# Taito_Arkanoid_paddle.net
KiCad netlist of a schematic drawn in EAGLE
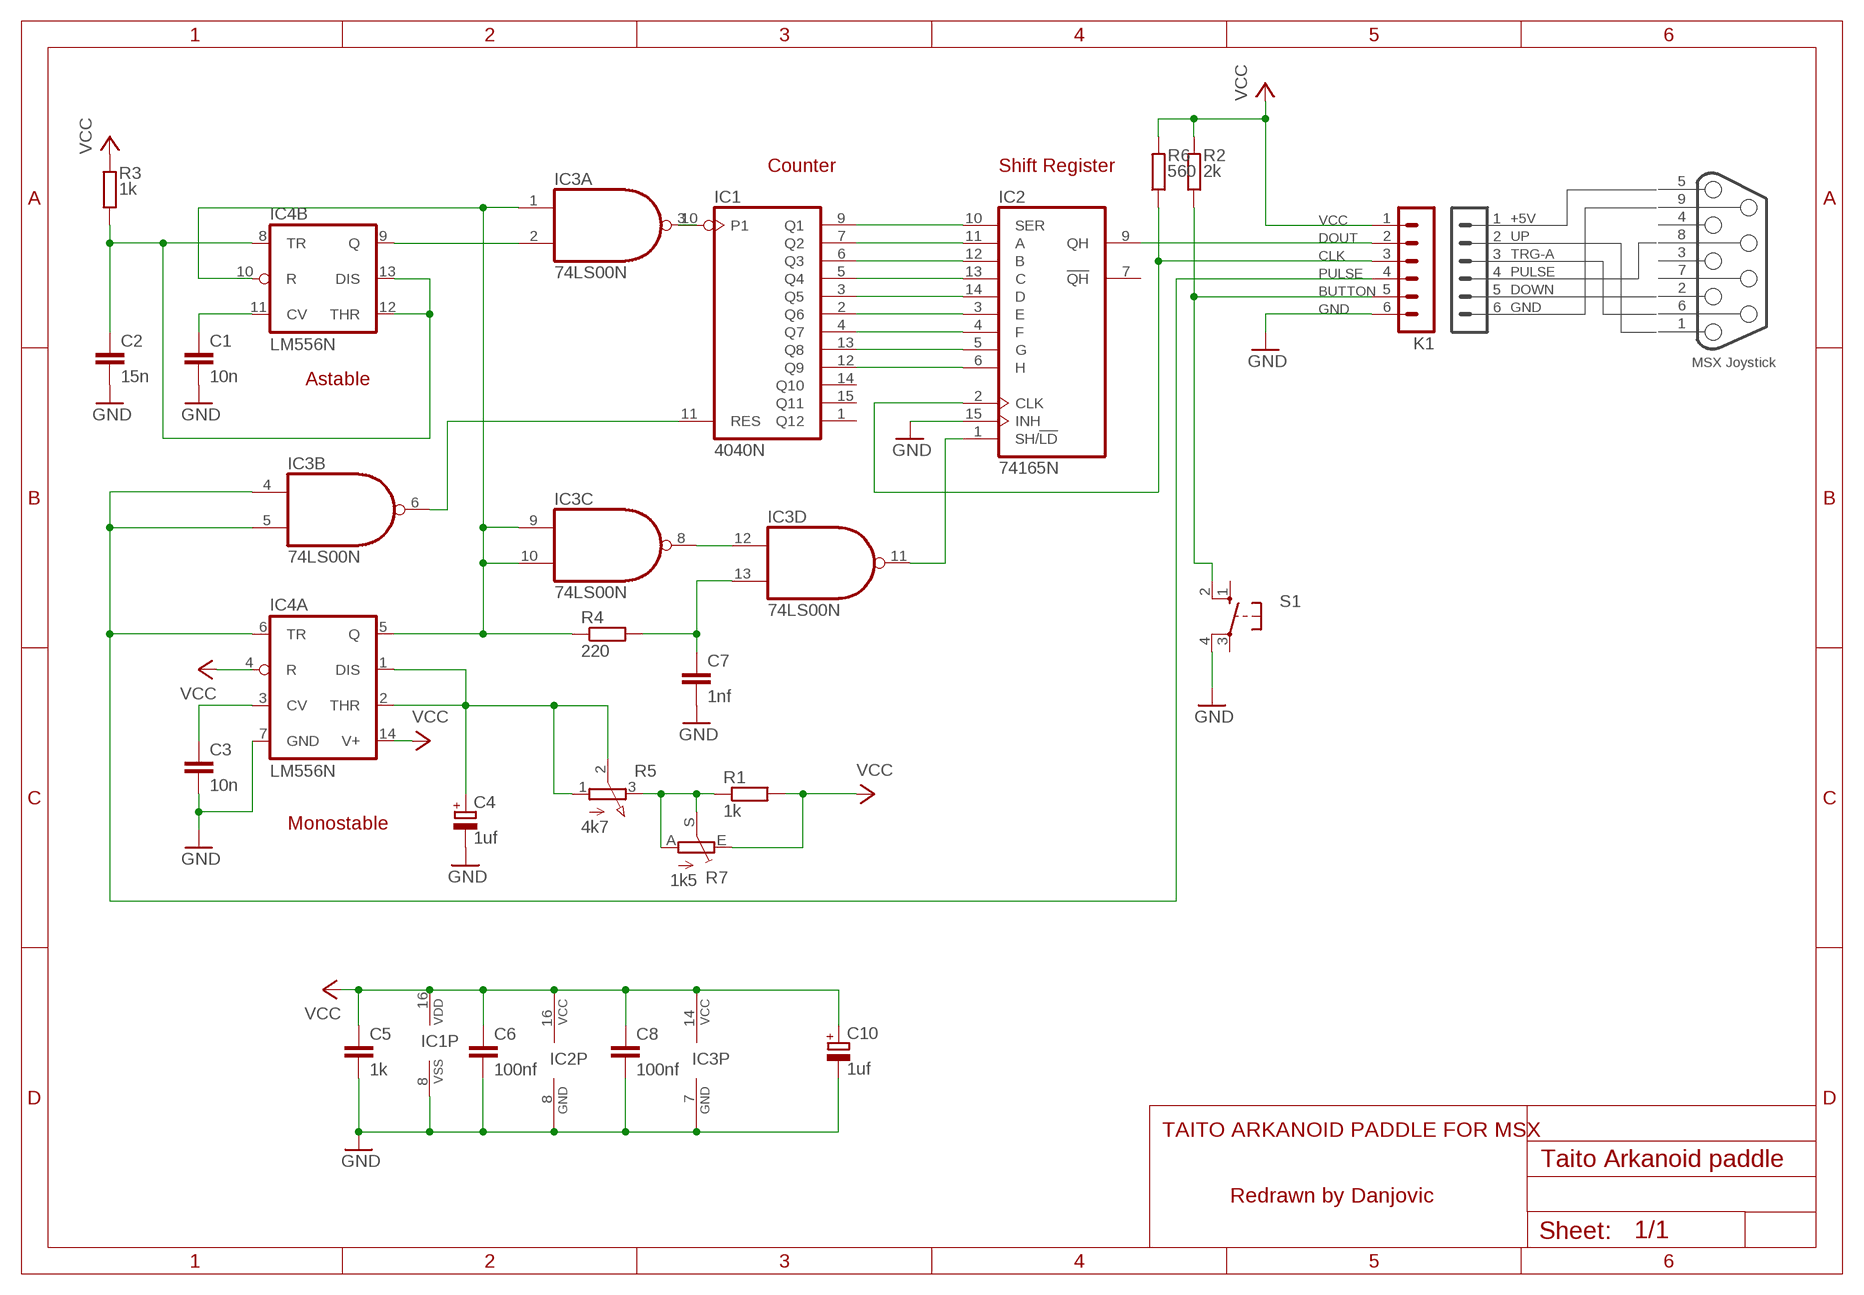
[diagram p0: schematic, sheet 1]

(export (version "E")
  (design (tool "Eeschema 10.0.6"))
  (components
    (comp (ref "C1")
      (value "10n")
      (footprint "eagle-import:C050-024X044")
      (libsource (lib "eagle-import") (part "C-EU050-024X044"))
    )
    (comp (ref "C2")
      (value "15n")
      (footprint "eagle-import:C050-024X044")
      (libsource (lib "eagle-import") (part "C-EU050-024X044"))
    )
    (comp (ref "C3")
      (value "10n")
      (footprint "eagle-import:C050-024X044")
      (libsource (lib "eagle-import") (part "C-EU050-024X044"))
    )
    (comp (ref "C4")
      (value "1uf")
      (footprint "eagle-import:E2-4")
      (libsource (lib "eagle-import") (part "CPOL-EUE2-4"))
    )
    (comp (ref "C5")
      (value "1k")
      (footprint "eagle-import:C050-024X044")
      (libsource (lib "eagle-import") (part "C-EU050-024X044"))
    )
    (comp (ref "C6")
      (value "100nf")
      (footprint "eagle-import:C050-024X044")
      (libsource (lib "eagle-import") (part "C-EU050-024X044"))
    )
    (comp (ref "C7")
      (value "1nf")
      (footprint "eagle-import:C050-024X044")
      (libsource (lib "eagle-import") (part "C-EU050-024X044"))
    )
    (comp (ref "C8")
      (value "100nf")
      (footprint "eagle-import:C050-024X044")
      (libsource (lib "eagle-import") (part "C-EU050-024X044"))
    )
    (comp (ref "C10")
      (value "1uf")
      (footprint "eagle-import:E2-4")
      (libsource (lib "eagle-import") (part "CPOL-EUE2-4"))
    )
    (comp (ref "IC1")
      (value "4040N")
      (footprint "eagle-import:DIL16")
      (libsource (lib "eagle-import") (part "4040N"))
    )
    (comp (ref "IC2")
      (value "74165N")
      (footprint "eagle-import:DIL16")
      (libsource (lib "eagle-import") (part "74165N"))
    )
    (comp (ref "IC3")
      (value "74LS00N")
      (footprint "eagle-import:DIL14")
      (libsource (lib "eagle-import") (part "7400NLS"))
    )
    (comp (ref "IC4")
      (value "LM556N")
      (footprint "eagle-import:DIL14")
      (libsource (lib "eagle-import") (part "556NLM"))
    )
    (comp (ref "K1")
      (value "MA06-1")
      (footprint "eagle-import:MA06-1")
      (libsource (lib "eagle-import") (part "MA06-1"))
    )
    (comp (ref "R1")
      (value "1k")
      (footprint "eagle-import:0207_7")
      (libsource (lib "eagle-import") (part "R-EU_0207/7"))
    )
    (comp (ref "R2")
      (value "2k")
      (footprint "eagle-import:0207_7")
      (libsource (lib "eagle-import") (part "R-EU_0207/7"))
    )
    (comp (ref "R3")
      (value "1k")
      (footprint "eagle-import:0207_7")
      (libsource (lib "eagle-import") (part "R-EU_0207/7"))
    )
    (comp (ref "R4")
      (value "220")
      (footprint "eagle-import:0207_7")
      (libsource (lib "eagle-import") (part "R-EU_0207/7"))
    )
    (comp (ref "R5")
      (value "4k7")
      (footprint "eagle-import:3RP_1610N_THRU")
      (libsource (lib "eagle-import") (part "3RP/1610NTHRU"))
    )
    (comp (ref "R6")
      (value "560")
      (footprint "eagle-import:0207_7")
      (libsource (lib "eagle-import") (part "R-EU_0207/7"))
    )
    (comp (ref "R7")
      (value "1k5")
      (footprint "eagle-import:CT6")
      (libsource (lib "eagle-import") (part "TRIM_EU-CT6"))
    )
    (comp (ref "S1")
      (value "40-XX")
      (footprint "eagle-import:B3F-40XX")
      (fields (field (name "MF") "OMRON COMPONENTS USA") (field (name "MPN") "B3F-4000"))
      (libsource (lib "eagle-import") (part "40-XX"))
    )
  )
  (nets
    (net (code "1") (name "/BUTTON") (class "Default")
      (node (ref "K1") (pin "5") (pinfunction "5_5") (pintype "passive"))
      (node (ref "R2") (pin "1") (pinfunction "1_1") (pintype "passive"))
      (node (ref "S1") (pin "2") (pinfunction "S1_2") (pintype "passive"))
    )
    (net (code "2") (name "/CLK") (class "Default")
      (node (ref "IC2") (pin "2") (pinfunction "CLK_2") (pintype "input"))
      (node (ref "K1") (pin "3") (pinfunction "3_3") (pintype "passive"))
      (node (ref "R6") (pin "1") (pinfunction "1_1") (pintype "passive"))
    )
    (net (code "3") (name "/DOUT") (class "Default")
      (node (ref "IC2") (pin "9") (pinfunction "QH_9") (pintype "output"))
      (node (ref "K1") (pin "2") (pinfunction "2_2") (pintype "passive"))
    )
    (net (code "4") (name "/PULSE") (class "Default")
      (node (ref "IC3") (pin "4") (pinfunction "I0_4") (pintype "input"))
      (node (ref "IC3") (pin "5") (pinfunction "I1_5") (pintype "input"))
      (node (ref "IC4") (pin "6") (pinfunction "TR_6") (pintype "input"))
      (node (ref "K1") (pin "4") (pinfunction "4_4") (pintype "passive"))
    )
    (net (code "5") (name "GND") (class "Default")
      (node (ref "C1") (pin "2") (pinfunction "2_2") (pintype "passive"))
      (node (ref "C10") (pin "-") (pinfunction "-_-") (pintype "passive"))
      (node (ref "C2") (pin "2") (pinfunction "2_2") (pintype "passive"))
      (node (ref "C3") (pin "2") (pinfunction "2_2") (pintype "passive"))
      (node (ref "C4") (pin "-") (pinfunction "-_-") (pintype "passive"))
      (node (ref "C5") (pin "2") (pinfunction "2_2") (pintype "passive"))
      (node (ref "C6") (pin "2") (pinfunction "2_2") (pintype "passive"))
      (node (ref "C7") (pin "2") (pinfunction "2_2") (pintype "passive"))
      (node (ref "C8") (pin "2") (pinfunction "2_2") (pintype "passive"))
      (node (ref "IC1") (pin "8") (pinfunction "VSS_8") (pintype "power_in"))
      (node (ref "IC2") (pin "15") (pinfunction "INH_15") (pintype "input"))
      (node (ref "IC2") (pin "8") (pinfunction "GND_8") (pintype "power_in"))
      (node (ref "IC3") (pin "7") (pinfunction "GND_7") (pintype "power_in"))
      (node (ref "IC4") (pin "7") (pinfunction "GND_7") (pintype "power_in"))
      (node (ref "K1") (pin "6") (pinfunction "6_6") (pintype "passive"))
      (node (ref "S1") (pin "4") (pinfunction "P1_4") (pintype "passive"))
    )
    (net (code "6") (name "Net-(IC1A-P1)") (class "Default")
      (node (ref "IC1") (pin "10") (pinfunction "P1_10") (pintype "input"))
      (node (ref "IC3") (pin "3") (pinfunction "O_3") (pintype "output"))
    )
    (net (code "7") (name "Net-(IC1A-Q1)") (class "Default")
      (node (ref "IC1") (pin "9") (pinfunction "Q1_9") (pintype "output"))
      (node (ref "IC2") (pin "10") (pinfunction "SER_10") (pintype "input"))
    )
    (net (code "8") (name "Net-(IC1A-Q2)") (class "Default")
      (node (ref "IC1") (pin "7") (pinfunction "Q2_7") (pintype "output"))
      (node (ref "IC2") (pin "11") (pinfunction "A_11") (pintype "input"))
    )
    (net (code "9") (name "Net-(IC1A-Q3)") (class "Default")
      (node (ref "IC1") (pin "6") (pinfunction "Q3_6") (pintype "output"))
      (node (ref "IC2") (pin "12") (pinfunction "B_12") (pintype "input"))
    )
    (net (code "10") (name "Net-(IC1A-Q4)") (class "Default")
      (node (ref "IC1") (pin "5") (pinfunction "Q4_5") (pintype "output"))
      (node (ref "IC2") (pin "13") (pinfunction "C_13") (pintype "input"))
    )
    (net (code "11") (name "Net-(IC1A-Q5)") (class "Default")
      (node (ref "IC1") (pin "3") (pinfunction "Q5_3") (pintype "output"))
      (node (ref "IC2") (pin "14") (pinfunction "D_14") (pintype "input"))
    )
    (net (code "12") (name "Net-(IC1A-Q6)") (class "Default")
      (node (ref "IC1") (pin "2") (pinfunction "Q6_2") (pintype "output"))
      (node (ref "IC2") (pin "3") (pinfunction "E_3") (pintype "input"))
    )
    (net (code "13") (name "Net-(IC1A-Q7)") (class "Default")
      (node (ref "IC1") (pin "4") (pinfunction "Q7_4") (pintype "output"))
      (node (ref "IC2") (pin "4") (pinfunction "F_4") (pintype "input"))
    )
    (net (code "14") (name "Net-(IC1A-Q8)") (class "Default")
      (node (ref "IC1") (pin "13") (pinfunction "Q8_13") (pintype "output"))
      (node (ref "IC2") (pin "5") (pinfunction "G_5") (pintype "input"))
    )
    (net (code "15") (name "Net-(IC1A-Q9)") (class "Default")
      (node (ref "IC1") (pin "12") (pinfunction "Q9_12") (pintype "output"))
      (node (ref "IC2") (pin "6") (pinfunction "H_6") (pintype "input"))
    )
    (net (code "16") (name "Net-(IC1A-RES)") (class "Default")
      (node (ref "IC1") (pin "11") (pinfunction "RES_11") (pintype "input"))
      (node (ref "IC3") (pin "6") (pinfunction "O_6") (pintype "output"))
    )
    (net (code "17") (name "Net-(IC2A-SH{slash}~{LD})") (class "Default")
      (node (ref "IC2") (pin "1") (pinfunction "SH/~{LD}_1") (pintype "input"))
      (node (ref "IC3") (pin "11") (pinfunction "O_11") (pintype "output"))
    )
    (net (code "18") (name "Net-(IC3A-I0)") (class "Default")
      (node (ref "IC3") (pin "1") (pinfunction "I0_1") (pintype "input"))
      (node (ref "IC3") (pin "10") (pinfunction "I1_10") (pintype "input"))
      (node (ref "IC3") (pin "9") (pinfunction "I0_9") (pintype "input"))
      (node (ref "IC4") (pin "10") (pinfunction "R_10") (pintype "input"))
      (node (ref "IC4") (pin "5") (pinfunction "Q_5") (pintype "output"))
      (node (ref "R4") (pin "1") (pinfunction "1_1") (pintype "passive"))
    )
    (net (code "19") (name "Net-(IC3A-I1)") (class "Default")
      (node (ref "IC3") (pin "2") (pinfunction "I1_2") (pintype "input"))
      (node (ref "IC4") (pin "9") (pinfunction "Q_9") (pintype "output"))
    )
    (net (code "20") (name "Net-(IC3C-O)") (class "Default")
      (node (ref "IC3") (pin "12") (pinfunction "I0_12") (pintype "input"))
      (node (ref "IC3") (pin "8") (pinfunction "O_8") (pintype "output"))
    )
    (net (code "21") (name "Net-(IC3D-I1)") (class "Default")
      (node (ref "C7") (pin "1") (pinfunction "1_1") (pintype "passive"))
      (node (ref "IC3") (pin "13") (pinfunction "I1_13") (pintype "input"))
      (node (ref "R4") (pin "2") (pinfunction "2_2") (pintype "passive"))
    )
    (net (code "22") (name "Net-(IC4A-CV)") (class "Default")
      (node (ref "C3") (pin "1") (pinfunction "1_1") (pintype "passive"))
      (node (ref "IC4") (pin "3") (pinfunction "CV_3") (pintype "input"))
    )
    (net (code "23") (name "Net-(IC4A-DIS)") (class "Default")
      (node (ref "C4") (pin "+") (pinfunction "+_+") (pintype "passive"))
      (node (ref "IC4") (pin "1") (pinfunction "DIS_1") (pintype "input"))
      (node (ref "IC4") (pin "2") (pinfunction "THR_2") (pintype "input"))
      (node (ref "R5") (pin "1") (pinfunction "A_1") (pintype "passive"))
      (node (ref "R5") (pin "2") (pinfunction "S_2") (pintype "passive"))
    )
    (net (code "24") (name "Net-(IC4B-CV)") (class "Default")
      (node (ref "C1") (pin "1") (pinfunction "1_1") (pintype "passive"))
      (node (ref "IC4") (pin "11") (pinfunction "CV_11") (pintype "input"))
    )
    (net (code "25") (name "Net-(IC4B-DIS)") (class "Default")
      (node (ref "C2") (pin "1") (pinfunction "1_1") (pintype "passive"))
      (node (ref "IC4") (pin "12") (pinfunction "THR_12") (pintype "input"))
      (node (ref "IC4") (pin "13") (pinfunction "DIS_13") (pintype "input"))
      (node (ref "IC4") (pin "8") (pinfunction "TR_8") (pintype "input"))
      (node (ref "R3") (pin "1") (pinfunction "1_1") (pintype "passive"))
    )
    (net (code "26") (name "Net-(R5-E)") (class "Default")
      (node (ref "R1") (pin "1") (pinfunction "1_1") (pintype "passive"))
      (node (ref "R5") (pin "3") (pinfunction "E_3") (pintype "passive"))
      (node (ref "R7") (pin "A") (pinfunction "A_A") (pintype "passive"))
      (node (ref "R7") (pin "S") (pinfunction "S_S") (pintype "passive"))
    )
    (net (code "27") (name "VCC") (class "Default")
      (node (ref "C10") (pin "+") (pinfunction "+_+") (pintype "passive"))
      (node (ref "C5") (pin "1") (pinfunction "1_1") (pintype "passive"))
      (node (ref "C6") (pin "1") (pinfunction "1_1") (pintype "passive"))
      (node (ref "C8") (pin "1") (pinfunction "1_1") (pintype "passive"))
      (node (ref "IC1") (pin "16") (pinfunction "VDD_16") (pintype "power_in"))
      (node (ref "IC2") (pin "16") (pinfunction "VCC_16") (pintype "power_in"))
      (node (ref "IC3") (pin "14") (pinfunction "VCC_14") (pintype "power_in"))
      (node (ref "IC4") (pin "14") (pinfunction "V+_14") (pintype "power_in"))
      (node (ref "IC4") (pin "4") (pinfunction "R_4") (pintype "input"))
      (node (ref "K1") (pin "1") (pinfunction "1_1") (pintype "passive"))
      (node (ref "R1") (pin "2") (pinfunction "2_2") (pintype "passive"))
      (node (ref "R2") (pin "2") (pinfunction "2_2") (pintype "passive"))
      (node (ref "R3") (pin "2") (pinfunction "2_2") (pintype "passive"))
      (node (ref "R6") (pin "2") (pinfunction "2_2") (pintype "passive"))
      (node (ref "R7") (pin "E") (pinfunction "E_E") (pintype "passive"))
    )
    (net (code "28") (name "unconnected-(IC1A-Q10-Pad14)") (class "Default")
      (node (ref "IC1") (pin "14") (pinfunction "Q10_14") (pintype "output"))
    )
    (net (code "29") (name "unconnected-(IC1A-Q11-Pad15)") (class "Default")
      (node (ref "IC1") (pin "15") (pinfunction "Q11_15") (pintype "output"))
    )
    (net (code "30") (name "unconnected-(IC1A-Q12-Pad1)") (class "Default")
      (node (ref "IC1") (pin "1") (pinfunction "Q12_1") (pintype "output"))
    )
    (net (code "31") (name "unconnected-(IC2A-~{QH}-Pad7)") (class "Default")
      (node (ref "IC2") (pin "7") (pinfunction "~{QH}_7") (pintype "output"))
    )
    (net (code "32") (name "unconnected-(S1-P-Pad3)") (class "Default")
      (node (ref "S1") (pin "3") (pinfunction "P_3") (pintype "passive"))
    )
    (net (code "33") (name "unconnected-(S1-S-Pad1)") (class "Default")
      (node (ref "S1") (pin "1") (pinfunction "S_1") (pintype "passive"))
    )
  )
)
